# MPU6050.net
KiCad netlist of a schematic drawn in Altium Designer
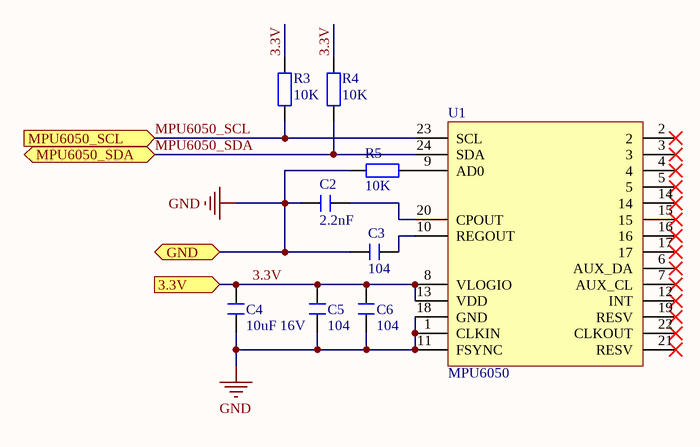
[diagram p0: MPU6050.SchDoc]

(export (version "E")
  (design (tool "Eeschema 10.0.6"))
  (components
    (comp (ref "C2")
      (value "2.2nF")
      (footprint "C 0603_L")
      (description "贴片电容")
      (libsource (lib "0.1 - 电阻-电容-电感") (part "C"))
    )
    (comp (ref "C3")
      (value "104")
      (footprint "C 0603_L")
      (description "贴片电容")
      (libsource (lib "0.1 - 电阻-电容-电感") (part "C"))
    )
    (comp (ref "C4")
      (value "10uF 16V")
      (footprint "C 0603_L")
      (description "贴片电容")
      (libsource (lib "0.1 - 电阻-电容-电感") (part "C"))
    )
    (comp (ref "C5")
      (value "104")
      (footprint "C 0603_L")
      (description "贴片电容")
      (libsource (lib "0.1 - 电阻-电容-电感") (part "C"))
    )
    (comp (ref "C6")
      (value "104")
      (footprint "C 0603_L")
      (description "贴片电容")
      (libsource (lib "0.1 - 电阻-电容-电感") (part "C"))
    )
    (comp (ref "R3")
      (value "10K")
      (footprint "R 0603_L")
      (description "贴片电阻")
      (libsource (lib "0.1 - 电阻-电容-电感") (part "R"))
    )
    (comp (ref "R4")
      (value "10K")
      (footprint "R 0603_L")
      (description "贴片电阻")
      (libsource (lib "0.1 - 电阻-电容-电感") (part "R"))
    )
    (comp (ref "R5")
      (value "10K")
      (footprint "R 0603_L")
      (description "贴片电阻")
      (libsource (lib "0.1 - 电阻-电容-电感") (part "R"))
    )
    (comp (ref "U1")
      (value "MPU6050")
      (footprint "QFN24 4x4_N")
      (description "三轴加速度+三轴陀螺仪")
      (libsource (lib "1.0 - 常见芯片") (part "MPU6050"))
    )
  )
  (nets
    (net (code "1") (name "/3.3V") (class "Default")
      (node (ref "C4") (pin "1") (pinfunction "1_1") (pintype "passive"))
      (node (ref "C5") (pin "1") (pinfunction "1_1") (pintype "passive"))
      (node (ref "C6") (pin "1") (pinfunction "1_1") (pintype "passive"))
      (node (ref "R3") (pin "1") (pinfunction "1_1") (pintype "passive"))
      (node (ref "R4") (pin "1") (pinfunction "1_1") (pintype "passive"))
      (node (ref "U1") (pin "13") (pinfunction "VDD_13") (pintype "passive"))
      (node (ref "U1") (pin "8") (pinfunction "VLOGIO_8") (pintype "passive"))
    )
    (net (code "2") (name "/MPU6050_SCL") (class "Default")
      (node (ref "R3") (pin "2") (pinfunction "2_2") (pintype "passive"))
      (node (ref "U1") (pin "23") (pinfunction "SCL_23") (pintype "passive"))
    )
    (net (code "3") (name "/MPU6050_SDA") (class "Default")
      (node (ref "R4") (pin "2") (pinfunction "2_2") (pintype "passive"))
      (node (ref "U1") (pin "24") (pinfunction "SDA_24") (pintype "passive"))
    )
    (net (code "4") (name "GND") (class "Default")
      (node (ref "C2") (pin "1") (pinfunction "1_1") (pintype "passive"))
      (node (ref "C3") (pin "1") (pinfunction "1_1") (pintype "passive"))
      (node (ref "C4") (pin "2") (pinfunction "2_2") (pintype "passive"))
      (node (ref "C5") (pin "2") (pinfunction "2_2") (pintype "passive"))
      (node (ref "C6") (pin "2") (pinfunction "2_2") (pintype "passive"))
      (node (ref "R5") (pin "1") (pinfunction "1_1") (pintype "passive"))
      (node (ref "U1") (pin "1") (pinfunction "CLKIN_1") (pintype "passive"))
      (node (ref "U1") (pin "11") (pinfunction "FSYNC_11") (pintype "passive"))
      (node (ref "U1") (pin "18") (pinfunction "GND_18") (pintype "passive"))
    )
    (net (code "5") (name "Net-(U1-AD0)") (class "Default")
      (node (ref "R5") (pin "2") (pinfunction "2_2") (pintype "passive"))
      (node (ref "U1") (pin "9") (pinfunction "AD0_9") (pintype "passive"))
    )
    (net (code "6") (name "Net-(U1-CPOUT)") (class "Default")
      (node (ref "C2") (pin "2") (pinfunction "2_2") (pintype "passive"))
      (node (ref "U1") (pin "20") (pinfunction "CPOUT_20") (pintype "passive"))
    )
    (net (code "7") (name "Net-(U1-REGOUT)") (class "Default")
      (node (ref "C3") (pin "2") (pinfunction "2_2") (pintype "passive"))
      (node (ref "U1") (pin "10") (pinfunction "REGOUT_10") (pintype "passive"))
    )
    (net (code "8") (name "unconnected-(U1-AUX_CL-Pad7)") (class "Default")
      (node (ref "U1") (pin "7") (pinfunction "AUX_CL_7") (pintype "passive+no_connect"))
    )
    (net (code "9") (name "unconnected-(U1-AUX_DA-Pad6)") (class "Default")
      (node (ref "U1") (pin "6") (pinfunction "AUX_DA_6") (pintype "passive+no_connect"))
    )
    (net (code "10") (name "unconnected-(U1-CLKOUT-Pad22)") (class "Default")
      (node (ref "U1") (pin "22") (pinfunction "CLKOUT_22") (pintype "passive+no_connect"))
    )
    (net (code "11") (name "unconnected-(U1-INT-Pad12)") (class "Default")
      (node (ref "U1") (pin "12") (pinfunction "INT_12") (pintype "passive+no_connect"))
    )
    (net (code "12") (name "unconnected-(U1-Pad2)") (class "Default")
      (node (ref "U1") (pin "2") (pinfunction "2_2") (pintype "passive+no_connect"))
    )
    (net (code "13") (name "unconnected-(U1-Pad3)") (class "Default")
      (node (ref "U1") (pin "3") (pinfunction "3_3") (pintype "passive+no_connect"))
    )
    (net (code "14") (name "unconnected-(U1-Pad4)") (class "Default")
      (node (ref "U1") (pin "4") (pinfunction "4_4") (pintype "passive+no_connect"))
    )
    (net (code "15") (name "unconnected-(U1-Pad5)") (class "Default")
      (node (ref "U1") (pin "5") (pinfunction "5_5") (pintype "passive+no_connect"))
    )
    (net (code "16") (name "unconnected-(U1-Pad14)") (class "Default")
      (node (ref "U1") (pin "14") (pinfunction "14_14") (pintype "passive+no_connect"))
    )
    (net (code "17") (name "unconnected-(U1-Pad15)") (class "Default")
      (node (ref "U1") (pin "15") (pinfunction "15_15") (pintype "passive+no_connect"))
    )
    (net (code "18") (name "unconnected-(U1-Pad16)") (class "Default")
      (node (ref "U1") (pin "16") (pinfunction "16_16") (pintype "passive+no_connect"))
    )
    (net (code "19") (name "unconnected-(U1-Pad17)") (class "Default")
      (node (ref "U1") (pin "17") (pinfunction "17_17") (pintype "passive+no_connect"))
    )
    (net (code "20") (name "unconnected-(U1-RESV-Pad19)") (class "Default")
      (node (ref "U1") (pin "19") (pinfunction "RESV_19") (pintype "passive+no_connect"))
    )
    (net (code "21") (name "unconnected-(U1-RESV-Pad21)") (class "Default")
      (node (ref "U1") (pin "21") (pinfunction "RESV_21") (pintype "passive+no_connect"))
    )
  )
)
